# TopLevel.net
KiCad netlist of a schematic drawn in Altium Designer
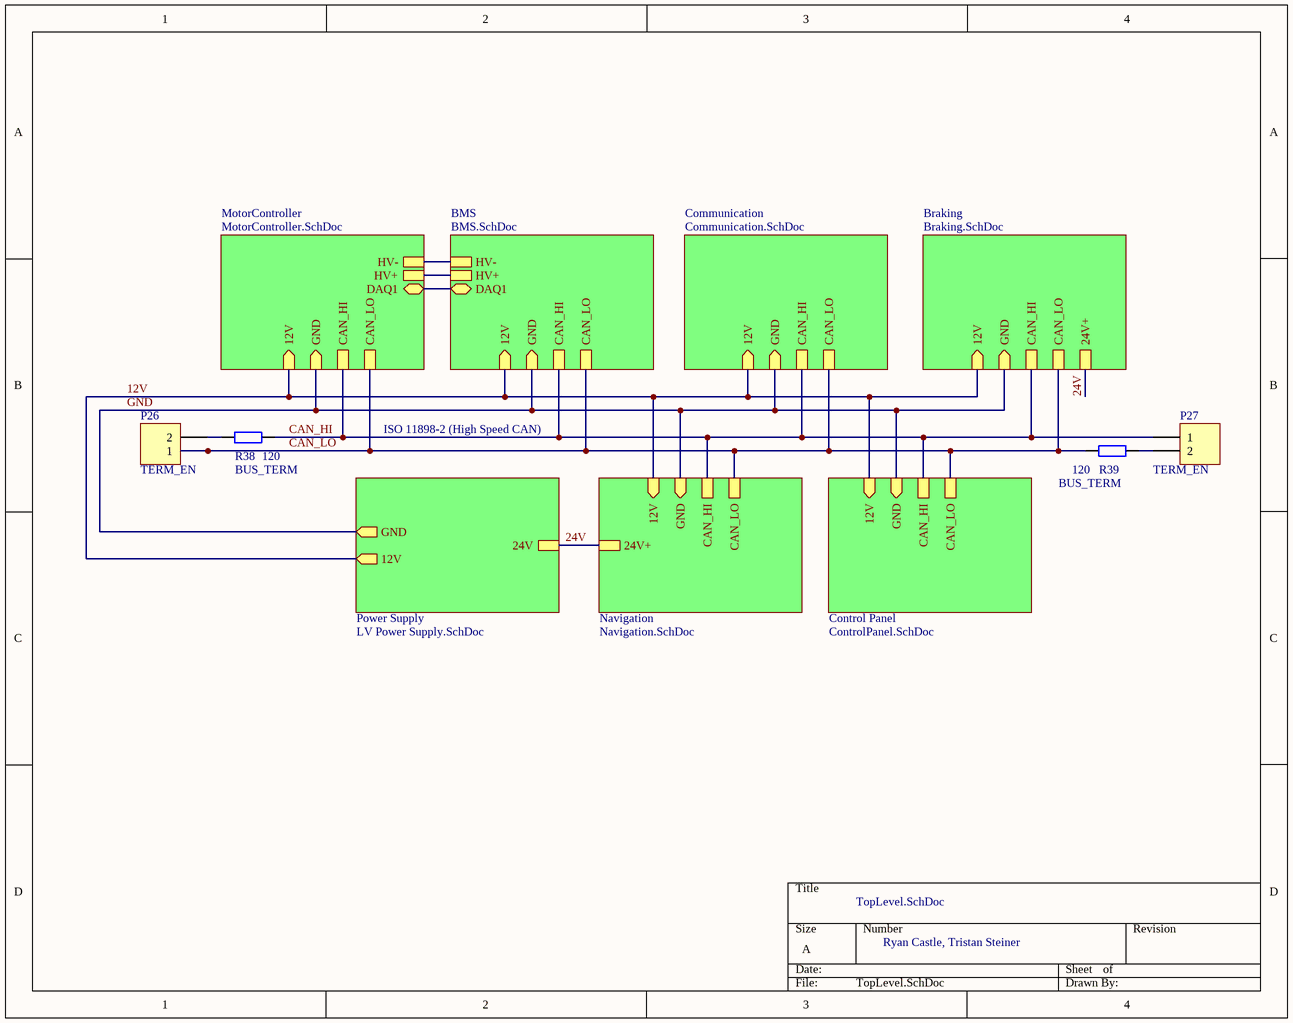
[diagram p0: TopLevel.SchDoc]

(export (version "E")
  (design (tool "Eeschema 10.0.6"))
  (components
    (comp (ref "P26")
      (value "TERM_EN")
      (footprint "HDR1X2")
      (description "Header, 2-Pin")
      (fields (field (name "PUBLISHER") "Altium Limited"))
      (libsource (lib "") (part "Header 2_1"))
    )
    (comp (ref "P27")
      (value "TERM_EN")
      (footprint "HDR1X2")
      (description "Header, 2-Pin")
      (fields (field (name "PUBLISHER") "Altium Limited"))
      (libsource (lib "Miscellaneous Connectors") (part "Header 2"))
    )
    (comp (ref "R38")
      (value "BUS_TERM")
      (footprint "AXIAL-0.4")
      (description "Resistor")
      (fields (field (name "ALTIUM_VALUE") "120") (field (name "PUBLISHER") "Altium Limited"))
      (libsource (lib "Miscellaneous Devices") (part "Res2"))
    )
    (comp (ref "R39")
      (value "BUS_TERM")
      (footprint "AXIAL-0.4")
      (description "Resistor")
      (fields (field (name "ALTIUM_VALUE") "120") (field (name "PUBLISHER") "Altium Limited"))
      (libsource (lib "Miscellaneous Devices") (part "Res2"))
    )
  )
  (nets
    (net (code "3") (name "/CAN_HI") (class "Default")
      (node (ref "P27") (pin "1") (pinfunction "1_1") (pintype "passive"))
      (node (ref "R38") (pin "2") (pinfunction "2_2") (pintype "passive"))
    )
    (net (code "4") (name "/CAN_LO") (class "Default")
      (node (ref "P26") (pin "1") (pinfunction "1_1") (pintype "passive"))
      (node (ref "R39") (pin "1") (pinfunction "1_1") (pintype "passive"))
    )
    (net (code "9") (name "Net-(P26-Pad2)") (class "Default")
      (node (ref "P26") (pin "2") (pinfunction "2_2") (pintype "passive"))
      (node (ref "R38") (pin "1") (pinfunction "1_1") (pintype "passive"))
    )
    (net (code "10") (name "Net-(P27-Pad2)") (class "Default")
      (node (ref "P27") (pin "2") (pinfunction "2_2") (pintype "passive"))
      (node (ref "R39") (pin "2") (pinfunction "2_2") (pintype "passive"))
    )
  )
)
